# 16053.net
KiCad netlist of a schematic drawn in EAGLE
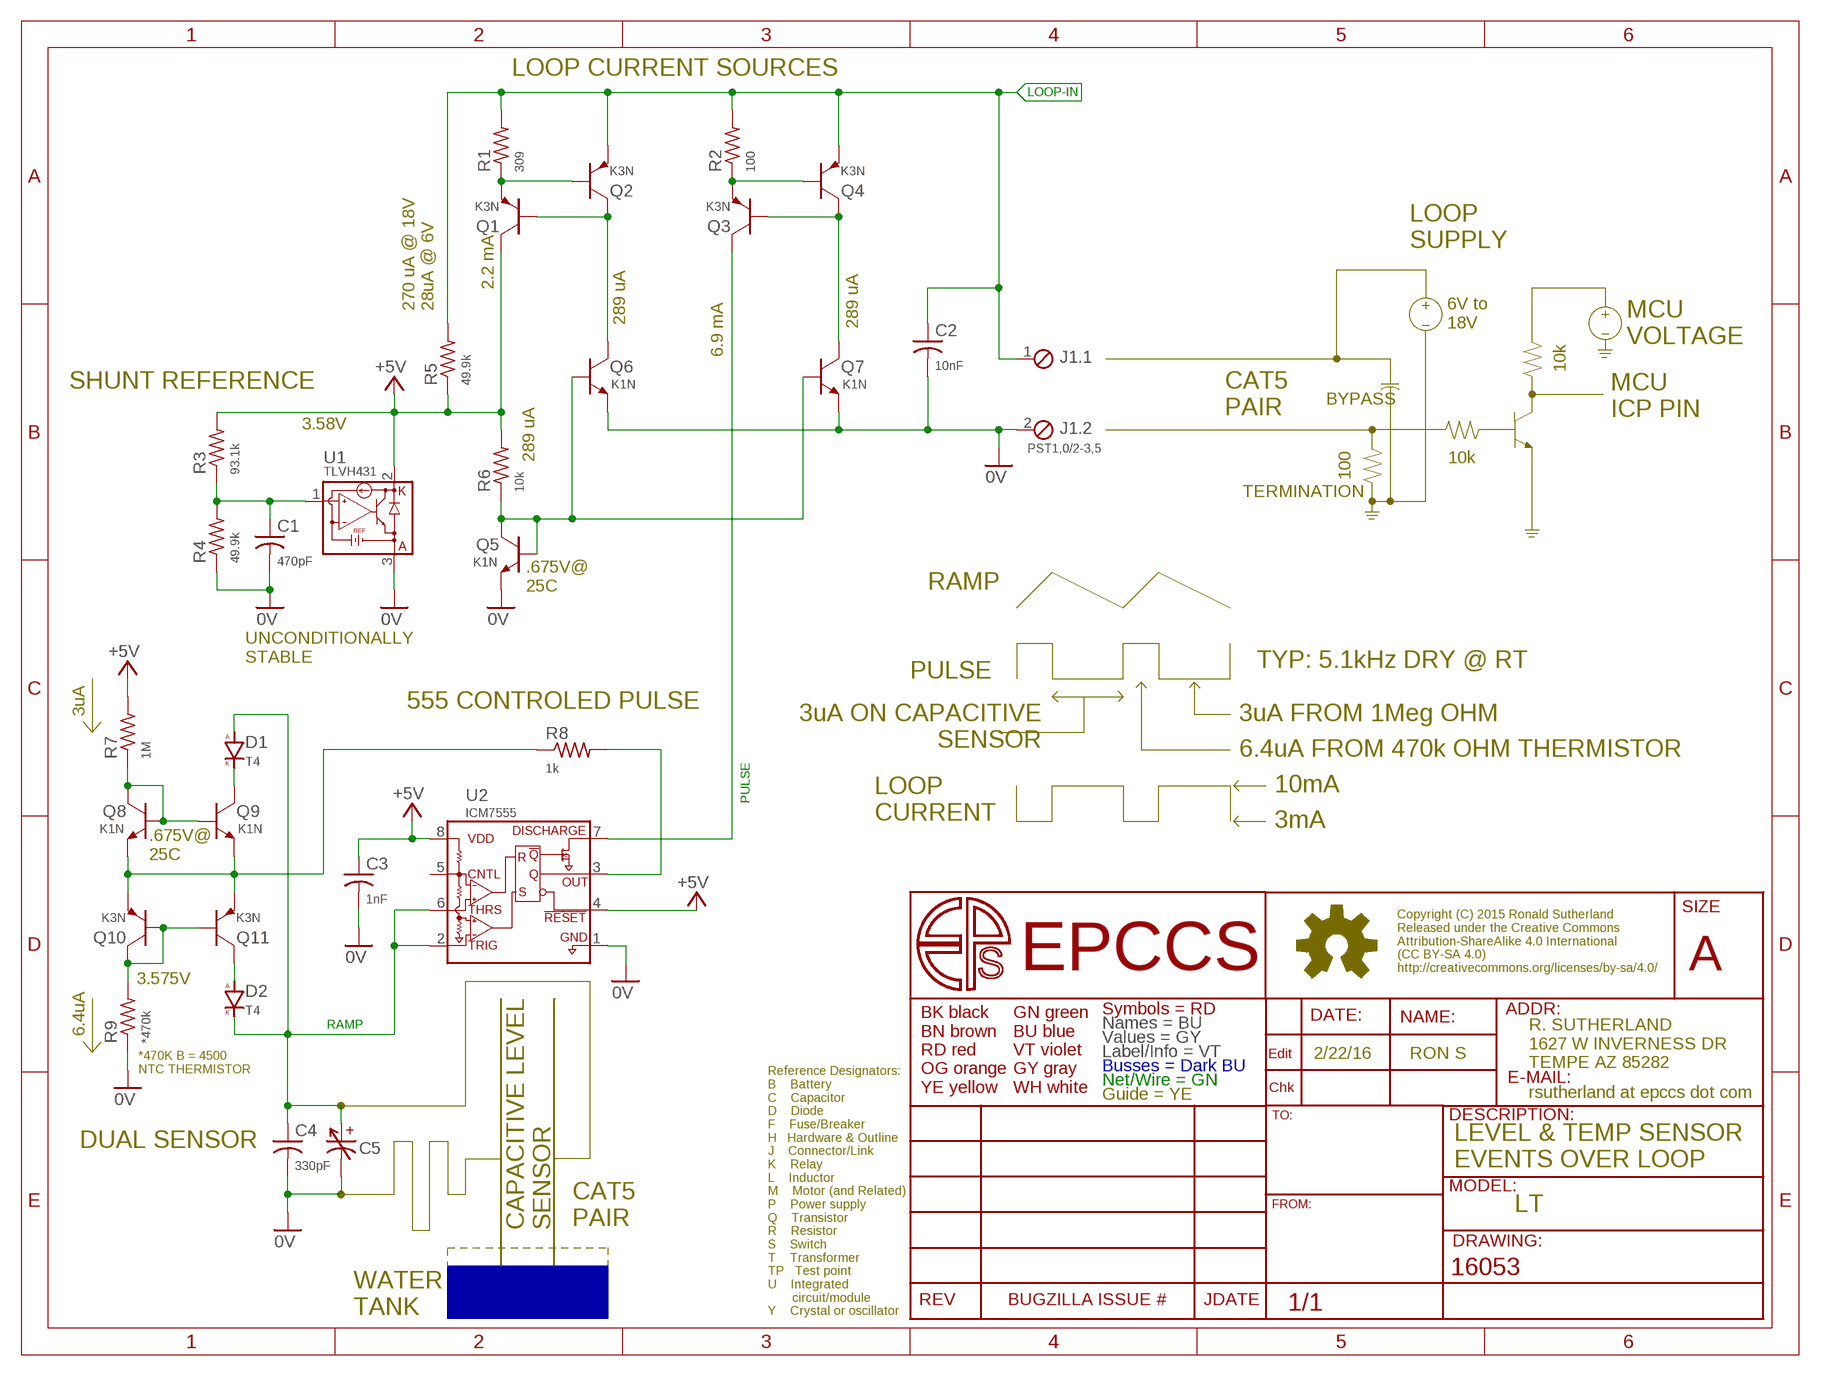
[diagram p0: schematic, sheet 1]

(export (version "E")
  (design (tool "Eeschema 10.0.6"))
  (components
    (comp (ref "C1")
      (value "470pF")
      (footprint "eagle-import:C0603(1608)")
      (libsource (lib "eagle-import") (part "CC0603A"))
    )
    (comp (ref "C2")
      (value "10nF")
      (footprint "eagle-import:C0603(1608)")
      (libsource (lib "eagle-import") (part "CC0603A"))
    )
    (comp (ref "C3")
      (value "1nF")
      (footprint "eagle-import:C0603(1608)")
      (libsource (lib "eagle-import") (part "CC0603A"))
    )
    (comp (ref "C4")
      (value "330pF")
      (footprint "eagle-import:C0603(1608)")
      (libsource (lib "eagle-import") (part "CC0603A"))
    )
    (comp (ref "C5")
      (value "HS1101")
      (footprint "eagle-import:HS1101")
      (libsource (lib "eagle-import") (part "HS1101"))
    )
    (comp (ref "D1")
      (value "T4")
      (footprint "eagle-import:SOD123")
      (libsource (lib "eagle-import") (part "DSOD123"))
    )
    (comp (ref "D2")
      (value "T4")
      (footprint "eagle-import:SOD123")
      (libsource (lib "eagle-import") (part "DSOD123"))
    )
    (comp (ref "J1")
      (value "PST1,0/2-3,5")
      (footprint "eagle-import:MCV2")
      (libsource (lib "eagle-import") (part "MCV2"))
    )
    (comp (ref "Q1")
      (value "K3N")
      (footprint "eagle-import:SOT23")
      (libsource (lib "eagle-import") (part "PNPSOT23"))
    )
    (comp (ref "Q2")
      (value "K3N")
      (footprint "eagle-import:SOT23")
      (libsource (lib "eagle-import") (part "PNPSOT23"))
    )
    (comp (ref "Q3")
      (value "K3N")
      (footprint "eagle-import:SOT23")
      (libsource (lib "eagle-import") (part "PNPSOT23"))
    )
    (comp (ref "Q4")
      (value "K3N")
      (footprint "eagle-import:SOT23")
      (libsource (lib "eagle-import") (part "PNPSOT23"))
    )
    (comp (ref "Q5")
      (value "K1N")
      (footprint "eagle-import:SOT23")
      (libsource (lib "eagle-import") (part "NPNSOT23"))
    )
    (comp (ref "Q6")
      (value "K1N")
      (footprint "eagle-import:SOT23")
      (libsource (lib "eagle-import") (part "NPNSOT23"))
    )
    (comp (ref "Q7")
      (value "K1N")
      (footprint "eagle-import:SOT23")
      (libsource (lib "eagle-import") (part "NPNSOT23"))
    )
    (comp (ref "Q8")
      (value "K1N")
      (footprint "eagle-import:SOT23")
      (libsource (lib "eagle-import") (part "NPNSOT23"))
    )
    (comp (ref "Q9")
      (value "K1N")
      (footprint "eagle-import:SOT23")
      (libsource (lib "eagle-import") (part "NPNSOT23"))
    )
    (comp (ref "Q10")
      (value "K3N")
      (footprint "eagle-import:SOT23")
      (libsource (lib "eagle-import") (part "PNPSOT23"))
    )
    (comp (ref "Q11")
      (value "K3N")
      (footprint "eagle-import:SOT23")
      (libsource (lib "eagle-import") (part "PNPSOT23"))
    )
    (comp (ref "R1")
      (value "309")
      (footprint "eagle-import:C0805(2012)")
      (libsource (lib "eagle-import") (part "R0805"))
    )
    (comp (ref "R2")
      (value "100")
      (footprint "eagle-import:C0805(2012)")
      (libsource (lib "eagle-import") (part "R0805"))
    )
    (comp (ref "R3")
      (value "93.1k")
      (footprint "eagle-import:C0805(2012)")
      (libsource (lib "eagle-import") (part "R0805"))
    )
    (comp (ref "R4")
      (value "49.9k")
      (footprint "eagle-import:C0805(2012)")
      (libsource (lib "eagle-import") (part "R0805"))
    )
    (comp (ref "R5")
      (value "49.9k")
      (footprint "eagle-import:C0805(2012)")
      (libsource (lib "eagle-import") (part "R0805"))
    )
    (comp (ref "R6")
      (value "10k")
      (footprint "eagle-import:C0805(2012)")
      (libsource (lib "eagle-import") (part "R0805"))
    )
    (comp (ref "R7")
      (value "1M")
      (footprint "eagle-import:C0805(2012)")
      (libsource (lib "eagle-import") (part "R0805"))
    )
    (comp (ref "R8")
      (value "1k")
      (footprint "eagle-import:C0805(2012)")
      (libsource (lib "eagle-import") (part "R0805"))
    )
    (comp (ref "R9")
      (value "*470k")
      (footprint "eagle-import:C0805(2012)")
      (libsource (lib "eagle-import") (part "R0805"))
    )
    (comp (ref "U1")
      (value "TLVH431")
      (footprint "eagle-import:SOT23")
      (libsource (lib "eagle-import") (part "TL432SOT23"))
    )
    (comp (ref "U2")
      (value "ICM7555")
      (footprint "eagle-import:SOIC8")
      (libsource (lib "eagle-import") (part "ICM7555"))
    )
  )
  (nets
    (net (code "1") (name "+5V") (class "Default")
      (node (ref "C3") (pin "1") (pinfunction "1_1") (pintype "passive"))
      (node (ref "Q1") (pin "C") (pinfunction "C_C") (pintype "passive"))
      (node (ref "R3") (pin "2") (pinfunction "2_2") (pintype "passive"))
      (node (ref "R5") (pin "1") (pinfunction "1_1") (pintype "passive"))
      (node (ref "R6") (pin "2") (pinfunction "2_2") (pintype "passive"))
      (node (ref "R7") (pin "2") (pinfunction "2_2") (pintype "passive"))
      (node (ref "U1") (pin "2") (pinfunction "K_2") (pintype "bidirectional"))
      (node (ref "U2") (pin "4") (pinfunction "~{RESET}_4") (pintype "input"))
      (node (ref "U2") (pin "8") (pinfunction "VDD_8") (pintype "power_in"))
    )
    (net (code "2") (name "/PULSE") (class "Default")
      (node (ref "Q3") (pin "C") (pinfunction "C_C") (pintype "passive"))
      (node (ref "U2") (pin "7") (pinfunction "DISCHARGE_7") (pintype "output"))
    )
    (net (code "3") (name "/RAMP") (class "Default")
      (node (ref "C4") (pin "1") (pinfunction "1_1") (pintype "passive"))
      (node (ref "C5") (pin "1") (pinfunction "1_1") (pintype "passive"))
      (node (ref "D1") (pin "A") (pinfunction "A_A") (pintype "passive"))
      (node (ref "D2") (pin "C") (pinfunction "K_C") (pintype "passive"))
      (node (ref "U2") (pin "2") (pinfunction "TRIG_2") (pintype "input"))
      (node (ref "U2") (pin "6") (pinfunction "THRS_6") (pintype "input"))
    )
    (net (code "4") (name "0V") (class "Default")
      (node (ref "C1") (pin "2") (pinfunction "2_2") (pintype "passive"))
      (node (ref "C2") (pin "2") (pinfunction "2_2") (pintype "passive"))
      (node (ref "C3") (pin "2") (pinfunction "2_2") (pintype "passive"))
      (node (ref "C4") (pin "2") (pinfunction "2_2") (pintype "passive"))
      (node (ref "C5") (pin "2") (pinfunction "2_2") (pintype "passive"))
      (node (ref "J1") (pin "2") (pinfunction "1_2") (pintype "passive"))
      (node (ref "Q5") (pin "E") (pinfunction "E_E") (pintype "passive"))
      (node (ref "Q6") (pin "E") (pinfunction "E_E") (pintype "passive"))
      (node (ref "Q7") (pin "E") (pinfunction "E_E") (pintype "passive"))
      (node (ref "R4") (pin "1") (pinfunction "1_1") (pintype "passive"))
      (node (ref "R9") (pin "1") (pinfunction "1_1") (pintype "passive"))
      (node (ref "U1") (pin "3") (pinfunction "A_3") (pintype "bidirectional"))
      (node (ref "U2") (pin "1") (pinfunction "GND_1") (pintype "power_in"))
    )
    (net (code "5") (name "LOOP-IN") (class "Default")
      (node (ref "C2") (pin "1") (pinfunction "1_1") (pintype "passive"))
      (node (ref "J1") (pin "1") (pinfunction "1_1") (pintype "passive"))
      (node (ref "Q2") (pin "E") (pinfunction "E_E") (pintype "passive"))
      (node (ref "Q4") (pin "E") (pinfunction "E_E") (pintype "passive"))
      (node (ref "R1") (pin "2") (pinfunction "2_2") (pintype "passive"))
      (node (ref "R2") (pin "2") (pinfunction "2_2") (pintype "passive"))
      (node (ref "R5") (pin "2") (pinfunction "2_2") (pintype "passive"))
    )
    (net (code "6") (name "Net-(D1-K)") (class "Default")
      (node (ref "D1") (pin "C") (pinfunction "K_C") (pintype "passive"))
      (node (ref "Q9") (pin "C") (pinfunction "C_C") (pintype "passive"))
    )
    (net (code "7") (name "Net-(D2-PadA)") (class "Default")
      (node (ref "D2") (pin "A") (pinfunction "A_A") (pintype "passive"))
      (node (ref "Q11") (pin "C") (pinfunction "C_C") (pintype "passive"))
    )
    (net (code "8") (name "Net-(Q1-PadB)") (class "Default")
      (node (ref "Q1") (pin "B") (pinfunction "B_B") (pintype "passive"))
      (node (ref "Q2") (pin "C") (pinfunction "C_C") (pintype "passive"))
      (node (ref "Q6") (pin "C") (pinfunction "C_C") (pintype "passive"))
    )
    (net (code "9") (name "Net-(Q1-PadE)") (class "Default")
      (node (ref "Q1") (pin "E") (pinfunction "E_E") (pintype "passive"))
      (node (ref "Q2") (pin "B") (pinfunction "B_B") (pintype "passive"))
      (node (ref "R1") (pin "1") (pinfunction "1_1") (pintype "passive"))
    )
    (net (code "10") (name "Net-(Q3-PadB)") (class "Default")
      (node (ref "Q3") (pin "B") (pinfunction "B_B") (pintype "passive"))
      (node (ref "Q4") (pin "C") (pinfunction "C_C") (pintype "passive"))
      (node (ref "Q7") (pin "C") (pinfunction "C_C") (pintype "passive"))
    )
    (net (code "11") (name "Net-(Q3-PadE)") (class "Default")
      (node (ref "Q3") (pin "E") (pinfunction "E_E") (pintype "passive"))
      (node (ref "Q4") (pin "B") (pinfunction "B_B") (pintype "passive"))
      (node (ref "R2") (pin "1") (pinfunction "1_1") (pintype "passive"))
    )
    (net (code "12") (name "Net-(Q5-PadB)") (class "Default")
      (node (ref "Q5") (pin "B") (pinfunction "B_B") (pintype "passive"))
      (node (ref "Q5") (pin "C") (pinfunction "C_C") (pintype "passive"))
      (node (ref "Q6") (pin "B") (pinfunction "B_B") (pintype "passive"))
      (node (ref "Q7") (pin "B") (pinfunction "B_B") (pintype "passive"))
      (node (ref "R6") (pin "1") (pinfunction "1_1") (pintype "passive"))
    )
    (net (code "13") (name "Net-(Q8-PadB)") (class "Default")
      (node (ref "Q8") (pin "B") (pinfunction "B_B") (pintype "passive"))
      (node (ref "Q8") (pin "C") (pinfunction "C_C") (pintype "passive"))
      (node (ref "Q9") (pin "B") (pinfunction "B_B") (pintype "passive"))
      (node (ref "R7") (pin "1") (pinfunction "1_1") (pintype "passive"))
    )
    (net (code "14") (name "Net-(Q10-PadB)") (class "Default")
      (node (ref "Q10") (pin "B") (pinfunction "B_B") (pintype "passive"))
      (node (ref "Q10") (pin "C") (pinfunction "C_C") (pintype "passive"))
      (node (ref "Q11") (pin "B") (pinfunction "B_B") (pintype "passive"))
      (node (ref "R9") (pin "2") (pinfunction "2_2") (pintype "passive"))
    )
    (net (code "15") (name "Net-(Q10-PadE)") (class "Default")
      (node (ref "Q10") (pin "E") (pinfunction "E_E") (pintype "passive"))
      (node (ref "Q11") (pin "E") (pinfunction "E_E") (pintype "passive"))
      (node (ref "Q8") (pin "E") (pinfunction "E_E") (pintype "passive"))
      (node (ref "Q9") (pin "E") (pinfunction "E_E") (pintype "passive"))
      (node (ref "R8") (pin "1") (pinfunction "1_1") (pintype "passive"))
    )
    (net (code "16") (name "Net-(U1-REF)") (class "Default")
      (node (ref "C1") (pin "1") (pinfunction "1_1") (pintype "passive"))
      (node (ref "R3") (pin "1") (pinfunction "1_1") (pintype "passive"))
      (node (ref "R4") (pin "2") (pinfunction "2_2") (pintype "passive"))
      (node (ref "U1") (pin "1") (pinfunction "REF_1") (pintype "bidirectional"))
    )
    (net (code "17") (name "Net-(U2-OUT)") (class "Default")
      (node (ref "R8") (pin "2") (pinfunction "2_2") (pintype "passive"))
      (node (ref "U2") (pin "3") (pinfunction "OUT_3") (pintype "output"))
    )
    (net (code "18") (name "unconnected-(U2-CNTL-Pad5)") (class "Default")
      (node (ref "U2") (pin "5") (pinfunction "CNTL_5") (pintype "bidirectional"))
    )
  )
)
